# MCP23017_PINOUT.net
KiCad netlist of a schematic drawn in Altium Designer
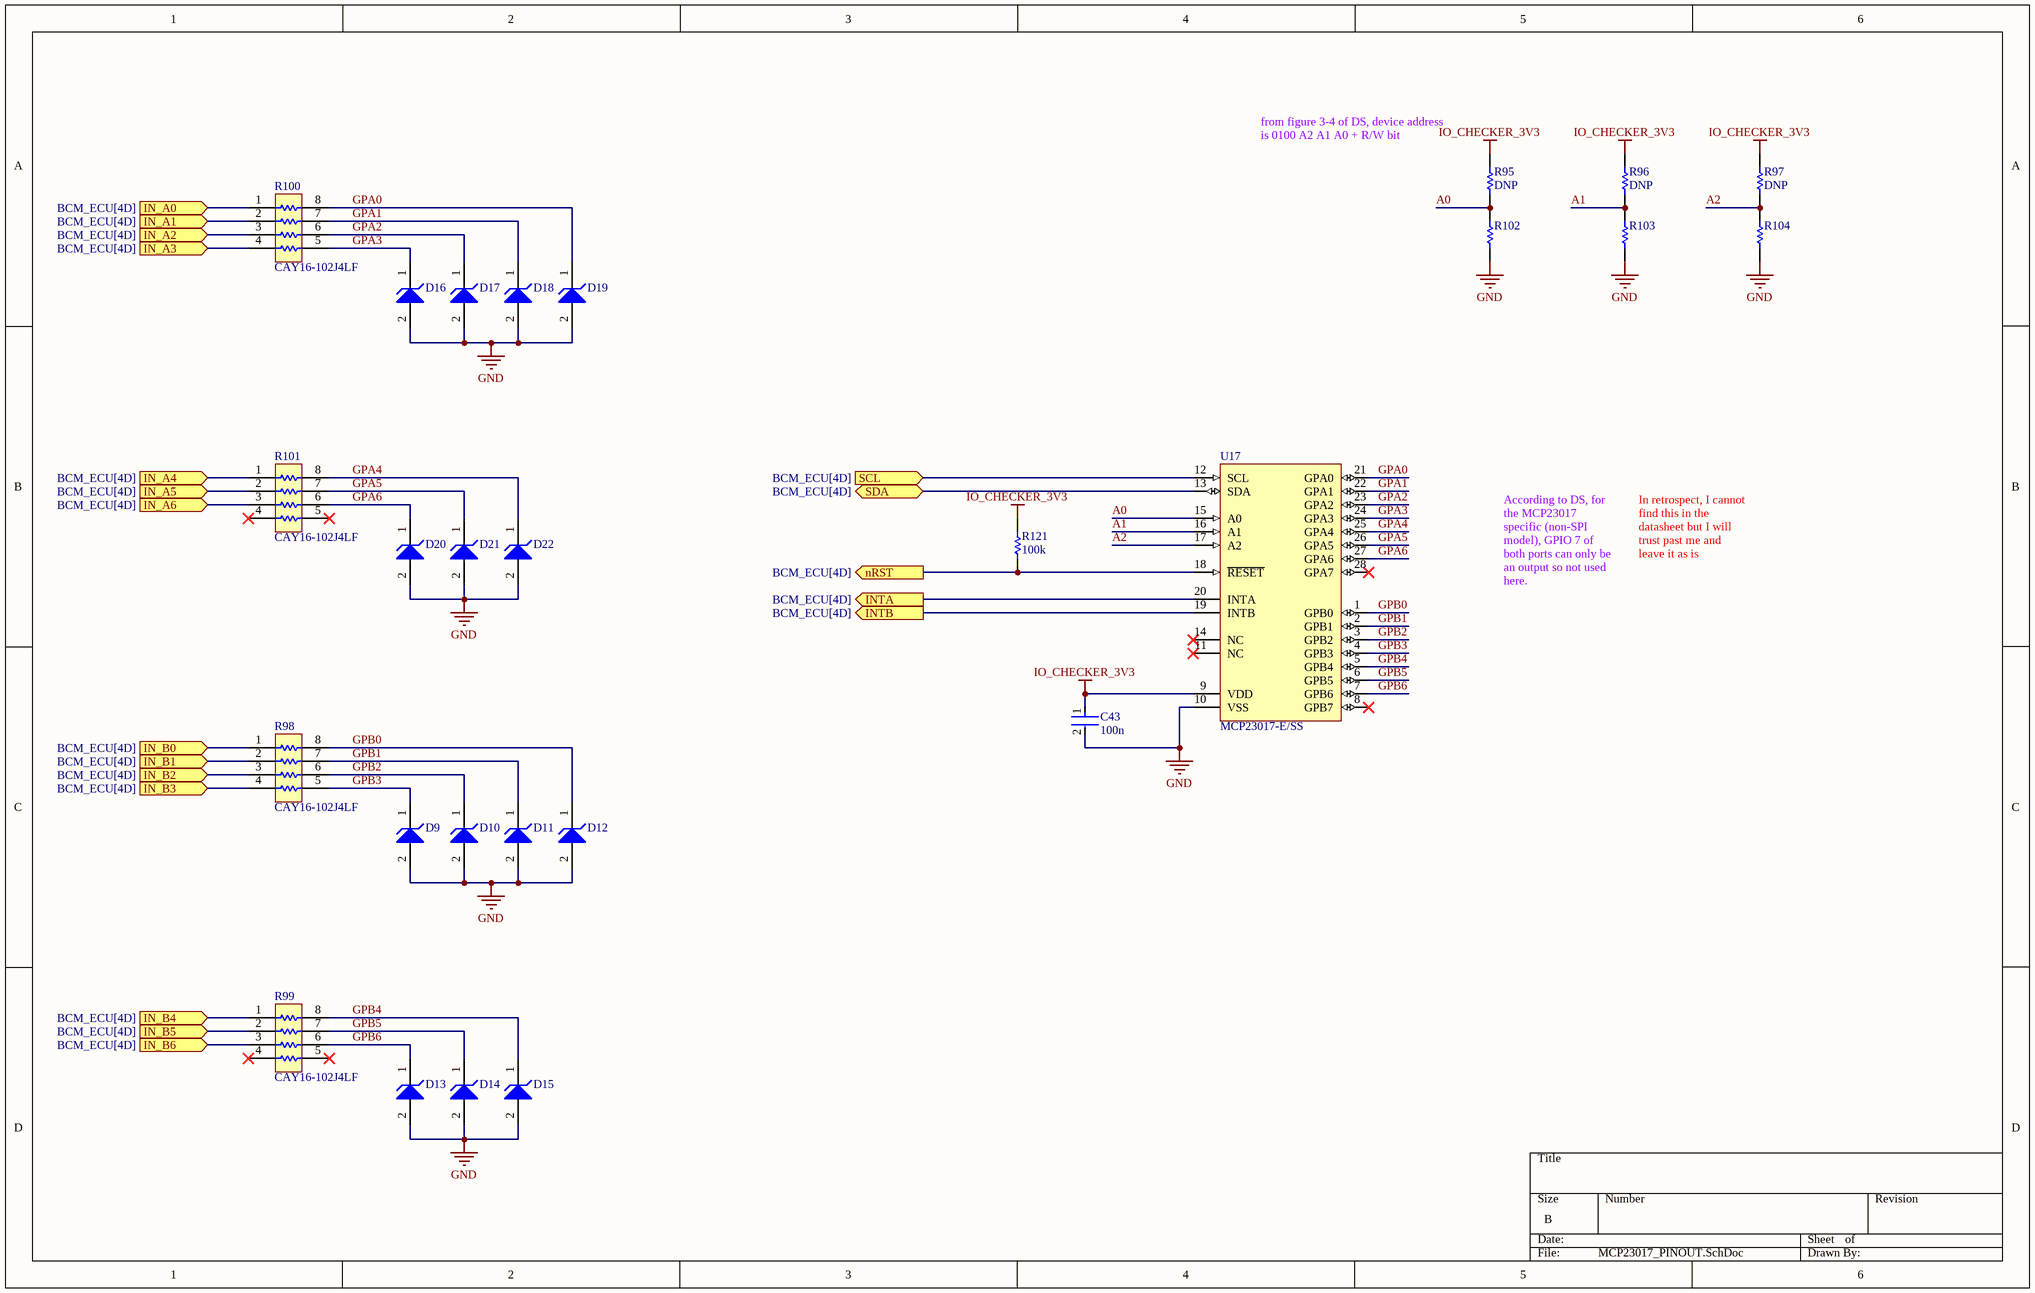
[diagram p0: MCP23017_PINOUT.SchDoc]

(export (version "E")
  (design (tool "Eeschema 10.0.6"))
  (components
    (comp (ref "C43")
      (value "100n")
      (footprint "FP-0402-L_1_0_0_05-W_0_5-IPC_A")
      (description "LARGE PADS, 0402 CAP, CHANGE COMMENT TO MATCH REAL P/N")
      (libsource (lib "Space Concordia") (part "b4654b650e69147ec39a6b967a45e02"))
    )
    (comp (ref "D9")
      (value "MM5Z3V3T1G")
      (footprint "ONSC-SOD-523-2-502-01_V")
      (description "Zener Voltage Regulator, 500 mW, 2-Pin SOD-523, Pb-Free, Tape and Reel")
      (fields (field (name "MANUFACTURER") "On Semiconductor"))
      (libsource (lib "Altium Content Vault") (part "ONSC-K1A2-2"))
    )
    (comp (ref "D10")
      (value "MM5Z3V3T1G")
      (footprint "ONSC-SOD-523-2-502-01_V")
      (description "Zener Voltage Regulator, 500 mW, 2-Pin SOD-523, Pb-Free, Tape and Reel")
      (fields (field (name "MANUFACTURER") "On Semiconductor"))
      (libsource (lib "Altium Content Vault") (part "ONSC-K1A2-2"))
    )
    (comp (ref "D11")
      (value "MM5Z3V3T1G")
      (footprint "ONSC-SOD-523-2-502-01_V")
      (description "Zener Voltage Regulator, 500 mW, 2-Pin SOD-523, Pb-Free, Tape and Reel")
      (fields (field (name "MANUFACTURER") "On Semiconductor"))
      (libsource (lib "Altium Content Vault") (part "ONSC-K1A2-2"))
    )
    (comp (ref "D12")
      (value "MM5Z3V3T1G")
      (footprint "ONSC-SOD-523-2-502-01_V")
      (description "Zener Voltage Regulator, 500 mW, 2-Pin SOD-523, Pb-Free, Tape and Reel")
      (fields (field (name "MANUFACTURER") "On Semiconductor"))
      (libsource (lib "Altium Content Vault") (part "ONSC-K1A2-2"))
    )
    (comp (ref "D13")
      (value "MM5Z3V3T1G")
      (footprint "ONSC-SOD-523-2-502-01_V")
      (description "Zener Voltage Regulator, 500 mW, 2-Pin SOD-523, Pb-Free, Tape and Reel")
      (fields (field (name "MANUFACTURER") "On Semiconductor"))
      (libsource (lib "Altium Content Vault") (part "ONSC-K1A2-2"))
    )
    (comp (ref "D14")
      (value "MM5Z3V3T1G")
      (footprint "ONSC-SOD-523-2-502-01_V")
      (description "Zener Voltage Regulator, 500 mW, 2-Pin SOD-523, Pb-Free, Tape and Reel")
      (fields (field (name "MANUFACTURER") "On Semiconductor"))
      (libsource (lib "Altium Content Vault") (part "ONSC-K1A2-2"))
    )
    (comp (ref "D15")
      (value "MM5Z3V3T1G")
      (footprint "ONSC-SOD-523-2-502-01_V")
      (description "Zener Voltage Regulator, 500 mW, 2-Pin SOD-523, Pb-Free, Tape and Reel")
      (fields (field (name "MANUFACTURER") "On Semiconductor"))
      (libsource (lib "Altium Content Vault") (part "ONSC-K1A2-2"))
    )
    (comp (ref "D16")
      (value "MM5Z3V3T1G")
      (footprint "ONSC-SOD-523-2-502-01_V")
      (description "Zener Voltage Regulator, 500 mW, 2-Pin SOD-523, Pb-Free, Tape and Reel")
      (fields (field (name "MANUFACTURER") "On Semiconductor"))
      (libsource (lib "Altium Content Vault") (part "ONSC-K1A2-2"))
    )
    (comp (ref "D17")
      (value "MM5Z3V3T1G")
      (footprint "ONSC-SOD-523-2-502-01_V")
      (description "Zener Voltage Regulator, 500 mW, 2-Pin SOD-523, Pb-Free, Tape and Reel")
      (fields (field (name "MANUFACTURER") "On Semiconductor"))
      (libsource (lib "Altium Content Vault") (part "ONSC-K1A2-2"))
    )
    (comp (ref "D18")
      (value "MM5Z3V3T1G")
      (footprint "ONSC-SOD-523-2-502-01_V")
      (description "Zener Voltage Regulator, 500 mW, 2-Pin SOD-523, Pb-Free, Tape and Reel")
      (fields (field (name "MANUFACTURER") "On Semiconductor"))
      (libsource (lib "Altium Content Vault") (part "ONSC-K1A2-2"))
    )
    (comp (ref "D19")
      (value "MM5Z3V3T1G")
      (footprint "ONSC-SOD-523-2-502-01_V")
      (description "Zener Voltage Regulator, 500 mW, 2-Pin SOD-523, Pb-Free, Tape and Reel")
      (fields (field (name "MANUFACTURER") "On Semiconductor"))
      (libsource (lib "Altium Content Vault") (part "ONSC-K1A2-2"))
    )
    (comp (ref "D20")
      (value "MM5Z3V3T1G")
      (footprint "ONSC-SOD-523-2-502-01_V")
      (description "Zener Voltage Regulator, 500 mW, 2-Pin SOD-523, Pb-Free, Tape and Reel")
      (fields (field (name "MANUFACTURER") "On Semiconductor"))
      (libsource (lib "Altium Content Vault") (part "ONSC-K1A2-2"))
    )
    (comp (ref "D21")
      (value "MM5Z3V3T1G")
      (footprint "ONSC-SOD-523-2-502-01_V")
      (description "Zener Voltage Regulator, 500 mW, 2-Pin SOD-523, Pb-Free, Tape and Reel")
      (fields (field (name "MANUFACTURER") "On Semiconductor"))
      (libsource (lib "Altium Content Vault") (part "ONSC-K1A2-2"))
    )
    (comp (ref "D22")
      (value "MM5Z3V3T1G")
      (footprint "ONSC-SOD-523-2-502-01_V")
      (description "Zener Voltage Regulator, 500 mW, 2-Pin SOD-523, Pb-Free, Tape and Reel")
      (fields (field (name "MANUFACTURER") "On Semiconductor"))
      (libsource (lib "Altium Content Vault") (part "ONSC-K1A2-2"))
    )
    (comp (ref "R95")
      (value "DNP")
      (footprint "R0603B")
      (description "Resistor")
      (libsource (lib "Space Concordia") (part "Resistor"))
    )
    (comp (ref "R96")
      (value "DNP")
      (footprint "R0603B")
      (description "Resistor")
      (libsource (lib "Space Concordia") (part "Resistor"))
    )
    (comp (ref "R97")
      (value "DNP")
      (footprint "R0603B")
      (description "Resistor")
      (libsource (lib "Space Concordia") (part "Resistor"))
    )
    (comp (ref "R98")
      (value "CAY16-102J4LF")
      (footprint "BOUR-CAY16-J4_V")
      (description "Chip Resistor Array, 1 KOhm, +/- 5%, 62.5 mW, -55 to 125 degC, 8-Pin SMD, RoHS, Tape and Reel")
      (fields (field (name "TOLERANCE") "1%"))
      (libsource (lib "Altium Content Vault") (part "RES-P-8"))
    )
    (comp (ref "R99")
      (value "CAY16-102J4LF")
      (footprint "BOUR-CAY16-J4_V")
      (description "Chip Resistor Array, 1 KOhm, +/- 5%, 62.5 mW, -55 to 125 degC, 8-Pin SMD, RoHS, Tape and Reel")
      (fields (field (name "TOLERANCE") "1%"))
      (libsource (lib "Altium Content Vault") (part "RES-P-8"))
    )
    (comp (ref "R100")
      (value "CAY16-102J4LF")
      (footprint "BOUR-CAY16-J4_V")
      (description "Chip Resistor Array, 1 KOhm, +/- 5%, 62.5 mW, -55 to 125 degC, 8-Pin SMD, RoHS, Tape and Reel")
      (fields (field (name "TOLERANCE") "1%"))
      (libsource (lib "Altium Content Vault") (part "RES-P-8"))
    )
    (comp (ref "R101")
      (value "CAY16-102J4LF")
      (footprint "BOUR-CAY16-J4_V")
      (description "Chip Resistor Array, 1 KOhm, +/- 5%, 62.5 mW, -55 to 125 degC, 8-Pin SMD, RoHS, Tape and Reel")
      (fields (field (name "TOLERANCE") "1%"))
      (libsource (lib "Altium Content Vault") (part "RES-P-8"))
    )
    (comp (ref "R102")
      (value "DNP")
      (footprint "RESC1005X40X25ML05T05")
      (description "READ THE NAME")
      (libsource (lib "Space Concordia") (part "CMP-009-00206-2"))
    )
    (comp (ref "R103")
      (value "DNP")
      (footprint "RESC1005X40X25ML05T05")
      (description "READ THE NAME")
      (libsource (lib "Space Concordia") (part "CMP-009-00206-2"))
    )
    (comp (ref "R104")
      (value "DNP")
      (footprint "RESC1005X40X25ML05T05")
      (description "READ THE NAME")
      (libsource (lib "Space Concordia") (part "CMP-009-00206-2"))
    )
    (comp (ref "R121")
      (value "100k")
      (footprint "R0603B")
      (description "Resistor")
      (libsource (lib "Space Concordia") (part "Resistor"))
    )
    (comp (ref "U17")
      (value "MCP23017-E/SS")
      (footprint "SSOP-SS28_N")
      (description "16-Bit I/O Expander with Serial Interface, 28-Pin SSOP, Extended Temperature")
      (libsource (lib "Altium Content Vault") (part "PR-BUSIC-MCP23017-28"))
    )
  )
  (nets
    (net (code "1") (name "/A0") (class "Default")
      (node (ref "R102") (pin "2") (pinfunction "2_2") (pintype "passive"))
      (node (ref "R95") (pin "1") (pinfunction "1_1") (pintype "passive"))
      (node (ref "U17") (pin "15") (pinfunction "A0_15") (pintype "input"))
    )
    (net (code "2") (name "/A1") (class "Default")
      (node (ref "R103") (pin "2") (pinfunction "2_2") (pintype "passive"))
      (node (ref "R96") (pin "1") (pinfunction "1_1") (pintype "passive"))
      (node (ref "U17") (pin "16") (pinfunction "A1_16") (pintype "input"))
    )
    (net (code "3") (name "/A2") (class "Default")
      (node (ref "R104") (pin "2") (pinfunction "2_2") (pintype "passive"))
      (node (ref "R97") (pin "1") (pinfunction "1_1") (pintype "passive"))
      (node (ref "U17") (pin "17") (pinfunction "A2_17") (pintype "input"))
    )
    (net (code "4") (name "/GPA0") (class "Default")
      (node (ref "D19") (pin "1") (pinfunction "K_1") (pintype "passive"))
      (node (ref "R100") (pin "8") (pinfunction "8_8") (pintype "passive"))
      (node (ref "U17") (pin "21") (pinfunction "GPA0_21") (pintype "bidirectional"))
    )
    (net (code "5") (name "/GPA1") (class "Default")
      (node (ref "D18") (pin "1") (pinfunction "K_1") (pintype "passive"))
      (node (ref "R100") (pin "7") (pinfunction "7_7") (pintype "passive"))
      (node (ref "U17") (pin "22") (pinfunction "GPA1_22") (pintype "bidirectional"))
    )
    (net (code "6") (name "/GPA2") (class "Default")
      (node (ref "D17") (pin "1") (pinfunction "K_1") (pintype "passive"))
      (node (ref "R100") (pin "6") (pinfunction "6_6") (pintype "passive"))
      (node (ref "U17") (pin "23") (pinfunction "GPA2_23") (pintype "bidirectional"))
    )
    (net (code "7") (name "/GPA3") (class "Default")
      (node (ref "D16") (pin "1") (pinfunction "K_1") (pintype "passive"))
      (node (ref "R100") (pin "5") (pinfunction "5_5") (pintype "passive"))
      (node (ref "U17") (pin "24") (pinfunction "GPA3_24") (pintype "bidirectional"))
    )
    (net (code "8") (name "/GPA4") (class "Default")
      (node (ref "D22") (pin "1") (pinfunction "K_1") (pintype "passive"))
      (node (ref "R101") (pin "8") (pinfunction "8_8") (pintype "passive"))
      (node (ref "U17") (pin "25") (pinfunction "GPA4_25") (pintype "bidirectional"))
    )
    (net (code "9") (name "/GPA5") (class "Default")
      (node (ref "D21") (pin "1") (pinfunction "K_1") (pintype "passive"))
      (node (ref "R101") (pin "7") (pinfunction "7_7") (pintype "passive"))
      (node (ref "U17") (pin "26") (pinfunction "GPA5_26") (pintype "bidirectional"))
    )
    (net (code "10") (name "/GPA6") (class "Default")
      (node (ref "D20") (pin "1") (pinfunction "K_1") (pintype "passive"))
      (node (ref "R101") (pin "6") (pinfunction "6_6") (pintype "passive"))
      (node (ref "U17") (pin "27") (pinfunction "GPA6_27") (pintype "bidirectional"))
    )
    (net (code "11") (name "/GPB0") (class "Default")
      (node (ref "D12") (pin "1") (pinfunction "K_1") (pintype "passive"))
      (node (ref "R98") (pin "8") (pinfunction "8_8") (pintype "passive"))
      (node (ref "U17") (pin "1") (pinfunction "GPB0_1") (pintype "bidirectional"))
    )
    (net (code "12") (name "/GPB1") (class "Default")
      (node (ref "D11") (pin "1") (pinfunction "K_1") (pintype "passive"))
      (node (ref "R98") (pin "7") (pinfunction "7_7") (pintype "passive"))
      (node (ref "U17") (pin "2") (pinfunction "GPB1_2") (pintype "bidirectional"))
    )
    (net (code "13") (name "/GPB2") (class "Default")
      (node (ref "D10") (pin "1") (pinfunction "K_1") (pintype "passive"))
      (node (ref "R98") (pin "6") (pinfunction "6_6") (pintype "passive"))
      (node (ref "U17") (pin "3") (pinfunction "GPB2_3") (pintype "bidirectional"))
    )
    (net (code "14") (name "/GPB3") (class "Default")
      (node (ref "D9") (pin "1") (pinfunction "K_1") (pintype "passive"))
      (node (ref "R98") (pin "5") (pinfunction "5_5") (pintype "passive"))
      (node (ref "U17") (pin "4") (pinfunction "GPB3_4") (pintype "bidirectional"))
    )
    (net (code "15") (name "/GPB4") (class "Default")
      (node (ref "D15") (pin "1") (pinfunction "K_1") (pintype "passive"))
      (node (ref "R99") (pin "8") (pinfunction "8_8") (pintype "passive"))
      (node (ref "U17") (pin "5") (pinfunction "GPB4_5") (pintype "bidirectional"))
    )
    (net (code "16") (name "/GPB5") (class "Default")
      (node (ref "D14") (pin "1") (pinfunction "K_1") (pintype "passive"))
      (node (ref "R99") (pin "7") (pinfunction "7_7") (pintype "passive"))
      (node (ref "U17") (pin "6") (pinfunction "GPB5_6") (pintype "bidirectional"))
    )
    (net (code "17") (name "/GPB6") (class "Default")
      (node (ref "D13") (pin "1") (pinfunction "K_1") (pintype "passive"))
      (node (ref "R99") (pin "6") (pinfunction "6_6") (pintype "passive"))
      (node (ref "U17") (pin "7") (pinfunction "GPB6_7") (pintype "bidirectional"))
    )
    (net (code "18") (name "/INTA") (class "Default")
      (node (ref "U17") (pin "20") (pinfunction "INTA_20") (pintype "open_collector"))
    )
    (net (code "19") (name "/INTB") (class "Default")
      (node (ref "U17") (pin "19") (pinfunction "INTB_19") (pintype "open_collector"))
    )
    (net (code "20") (name "/IN_A0") (class "Default")
      (node (ref "R100") (pin "1") (pinfunction "1_1") (pintype "passive"))
    )
    (net (code "21") (name "/IN_A1") (class "Default")
      (node (ref "R100") (pin "2") (pinfunction "2_2") (pintype "passive"))
    )
    (net (code "22") (name "/IN_A2") (class "Default")
      (node (ref "R100") (pin "3") (pinfunction "3_3") (pintype "passive"))
    )
    (net (code "23") (name "/IN_A3") (class "Default")
      (node (ref "R100") (pin "4") (pinfunction "4_4") (pintype "passive"))
    )
    (net (code "24") (name "/IN_A4") (class "Default")
      (node (ref "R101") (pin "1") (pinfunction "1_1") (pintype "passive"))
    )
    (net (code "25") (name "/IN_A5") (class "Default")
      (node (ref "R101") (pin "2") (pinfunction "2_2") (pintype "passive"))
    )
    (net (code "26") (name "/IN_A6") (class "Default")
      (node (ref "R101") (pin "3") (pinfunction "3_3") (pintype "passive"))
    )
    (net (code "27") (name "/IN_B0") (class "Default")
      (node (ref "R98") (pin "1") (pinfunction "1_1") (pintype "passive"))
    )
    (net (code "28") (name "/IN_B1") (class "Default")
      (node (ref "R98") (pin "2") (pinfunction "2_2") (pintype "passive"))
    )
    (net (code "29") (name "/IN_B2") (class "Default")
      (node (ref "R98") (pin "3") (pinfunction "3_3") (pintype "passive"))
    )
    (net (code "30") (name "/IN_B3") (class "Default")
      (node (ref "R98") (pin "4") (pinfunction "4_4") (pintype "passive"))
    )
    (net (code "31") (name "/IN_B4") (class "Default")
      (node (ref "R99") (pin "1") (pinfunction "1_1") (pintype "passive"))
    )
    (net (code "32") (name "/IN_B5") (class "Default")
      (node (ref "R99") (pin "2") (pinfunction "2_2") (pintype "passive"))
    )
    (net (code "33") (name "/IN_B6") (class "Default")
      (node (ref "R99") (pin "3") (pinfunction "3_3") (pintype "passive"))
    )
    (net (code "34") (name "/SCL") (class "Default")
      (node (ref "U17") (pin "12") (pinfunction "SCL_12") (pintype "input"))
    )
    (net (code "35") (name "/SDA") (class "Default")
      (node (ref "U17") (pin "13") (pinfunction "SDA_13") (pintype "bidirectional"))
    )
    (net (code "36") (name "/nRST") (class "Default")
      (node (ref "R121") (pin "1") (pinfunction "1_1") (pintype "passive"))
      (node (ref "U17") (pin "18") (pinfunction "~{RESET}_18") (pintype "input"))
    )
    (net (code "37") (name "GND") (class "Default")
      (node (ref "C43") (pin "2") (pinfunction "2_2") (pintype "passive"))
      (node (ref "D10") (pin "2") (pinfunction "A_2") (pintype "passive"))
      (node (ref "D11") (pin "2") (pinfunction "A_2") (pintype "passive"))
      (node (ref "D12") (pin "2") (pinfunction "A_2") (pintype "passive"))
      (node (ref "D13") (pin "2") (pinfunction "A_2") (pintype "passive"))
      (node (ref "D14") (pin "2") (pinfunction "A_2") (pintype "passive"))
      (node (ref "D15") (pin "2") (pinfunction "A_2") (pintype "passive"))
      (node (ref "D16") (pin "2") (pinfunction "A_2") (pintype "passive"))
      (node (ref "D17") (pin "2") (pinfunction "A_2") (pintype "passive"))
      (node (ref "D18") (pin "2") (pinfunction "A_2") (pintype "passive"))
      (node (ref "D19") (pin "2") (pinfunction "A_2") (pintype "passive"))
      (node (ref "D20") (pin "2") (pinfunction "A_2") (pintype "passive"))
      (node (ref "D21") (pin "2") (pinfunction "A_2") (pintype "passive"))
      (node (ref "D22") (pin "2") (pinfunction "A_2") (pintype "passive"))
      (node (ref "D9") (pin "2") (pinfunction "A_2") (pintype "passive"))
      (node (ref "R102") (pin "1") (pinfunction "1_1") (pintype "passive"))
      (node (ref "R103") (pin "1") (pinfunction "1_1") (pintype "passive"))
      (node (ref "R104") (pin "1") (pinfunction "1_1") (pintype "passive"))
      (node (ref "U17") (pin "10") (pinfunction "VSS_10") (pintype "power_in"))
    )
    (net (code "38") (name "IO_CHECKER_3V3") (class "Default")
      (node (ref "C43") (pin "1") (pinfunction "1_1") (pintype "passive"))
      (node (ref "R121") (pin "2") (pinfunction "2_2") (pintype "passive"))
      (node (ref "R95") (pin "2") (pinfunction "2_2") (pintype "passive"))
      (node (ref "R96") (pin "2") (pinfunction "2_2") (pintype "passive"))
      (node (ref "R97") (pin "2") (pinfunction "2_2") (pintype "passive"))
      (node (ref "U17") (pin "9") (pinfunction "VDD_9") (pintype "power_in"))
    )
    (net (code "39") (name "unconnected-(R99-Pad4)") (class "Default")
      (node (ref "R99") (pin "4") (pinfunction "4_4") (pintype "passive+no_connect"))
    )
    (net (code "40") (name "unconnected-(R99-Pad5)") (class "Default")
      (node (ref "R99") (pin "5") (pinfunction "5_5") (pintype "passive+no_connect"))
    )
    (net (code "41") (name "unconnected-(R101-Pad4)") (class "Default")
      (node (ref "R101") (pin "4") (pinfunction "4_4") (pintype "passive+no_connect"))
    )
    (net (code "42") (name "unconnected-(R101-Pad5)") (class "Default")
      (node (ref "R101") (pin "5") (pinfunction "5_5") (pintype "passive+no_connect"))
    )
    (net (code "43") (name "unconnected-(U17-GPA7-Pad28)") (class "Default")
      (node (ref "U17") (pin "28") (pinfunction "GPA7_28") (pintype "bidirectional+no_connect"))
    )
    (net (code "44") (name "unconnected-(U17-GPB7-Pad8)") (class "Default")
      (node (ref "U17") (pin "8") (pinfunction "GPB7_8") (pintype "bidirectional+no_connect"))
    )
    (net (code "45") (name "unconnected-(U17-NC-Pad11)") (class "Default")
      (node (ref "U17") (pin "11") (pinfunction "NC_11") (pintype "passive+no_connect"))
    )
    (net (code "46") (name "unconnected-(U17-NC-Pad14)") (class "Default")
      (node (ref "U17") (pin "14") (pinfunction "NC_14") (pintype "passive+no_connect"))
    )
  )
)
